# WIRELESS_UART.net
KiCad netlist of a schematic drawn in Altium Designer
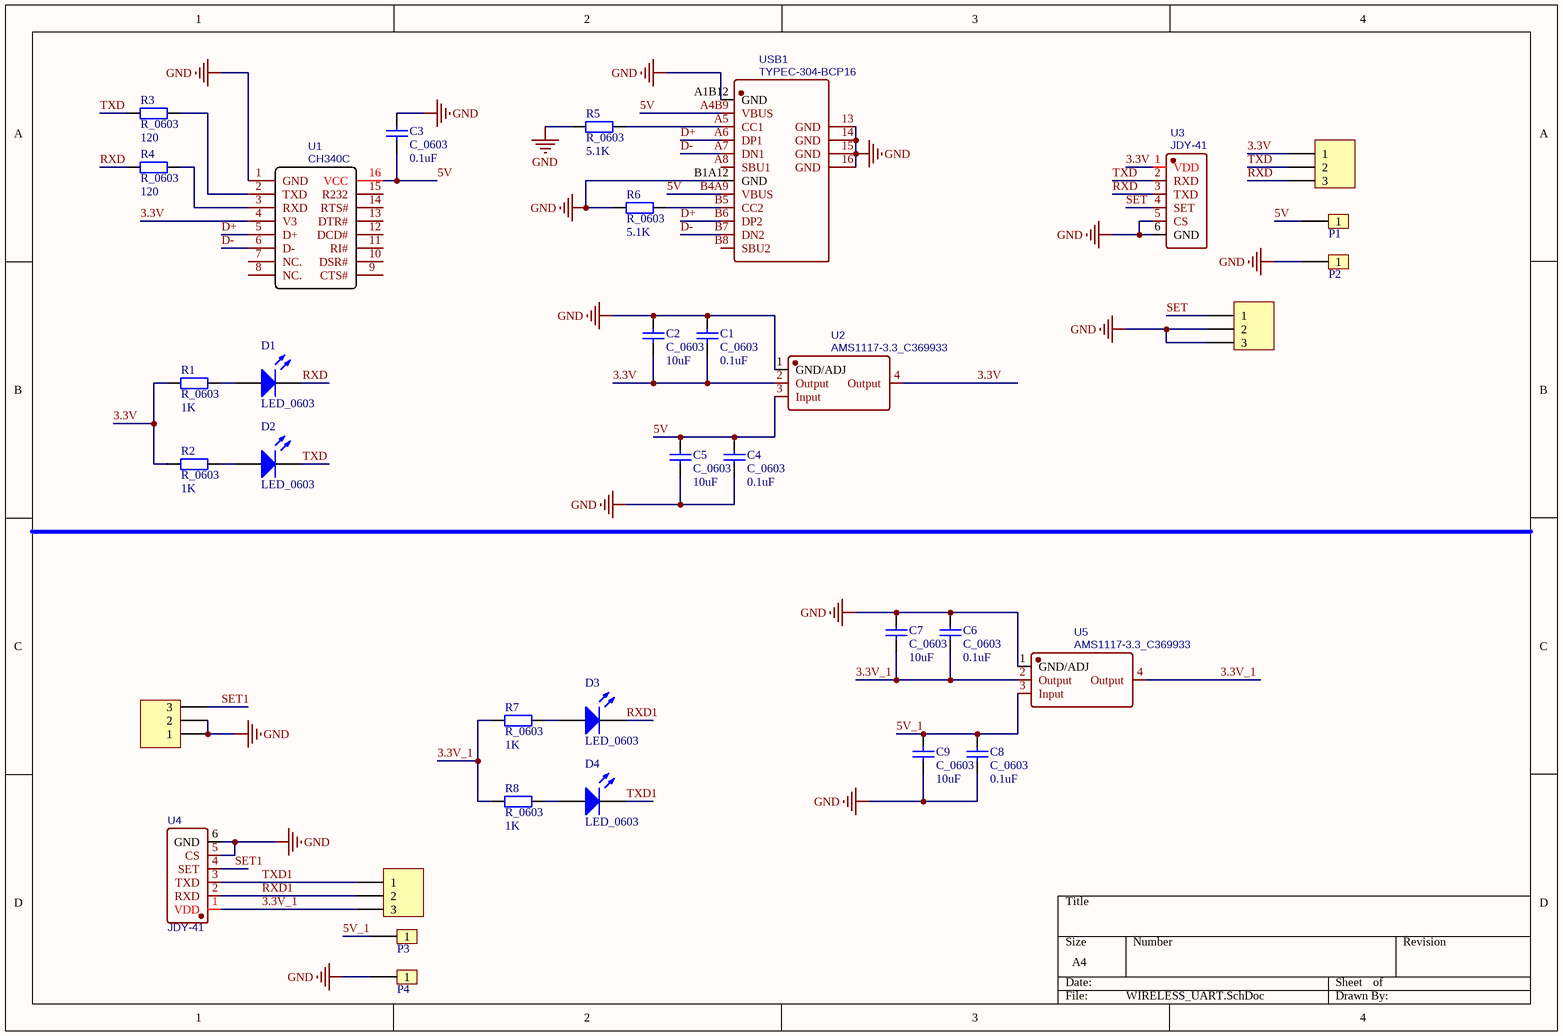
[diagram p0: WIRELESS_UART.SchDoc]

(export (version "E")
  (design (tool "Eeschema 10.0.6"))
  (components
    (comp (ref "C1")
      (value "C_0603")
      (footprint "C_0603")
      (fields (field (name "ALTIUM_VALUE") "0.1uF") (field (name "PUBLISHER") "Altium Limited"))
      (libsource (lib "WIRELESS_UART") (part "C_0603"))
    )
    (comp (ref "C2")
      (value "C_0603")
      (footprint "C1206 - duplicate")
      (fields (field (name "ALTIUM_VALUE") "10uF") (field (name "PUBLISHER") "Altium Limited"))
      (libsource (lib "WIRELESS_UART") (part "C_0603"))
    )
    (comp (ref "C3")
      (value "C_0603")
      (footprint "C_0603")
      (fields (field (name "ALTIUM_VALUE") "0.1uF") (field (name "PUBLISHER") "Altium Limited"))
      (libsource (lib "WIRELESS_UART") (part "C_0603"))
    )
    (comp (ref "C4")
      (value "C_0603")
      (footprint "C_0603")
      (fields (field (name "ALTIUM_VALUE") "0.1uF") (field (name "PUBLISHER") "Altium Limited"))
      (libsource (lib "WIRELESS_UART") (part "C_0603"))
    )
    (comp (ref "C5")
      (value "C_0603")
      (footprint "C1206 - duplicate")
      (fields (field (name "ALTIUM_VALUE") "10uF") (field (name "PUBLISHER") "Altium Limited"))
      (libsource (lib "WIRELESS_UART") (part "C_0603"))
    )
    (comp (ref "C6")
      (value "C_0603")
      (footprint "C_0603")
      (fields (field (name "ALTIUM_VALUE") "0.1uF") (field (name "PUBLISHER") "Altium Limited"))
      (libsource (lib "WIRELESS_UART") (part "C_0603"))
    )
    (comp (ref "C7")
      (value "C_0603")
      (footprint "C1206 - duplicate")
      (fields (field (name "ALTIUM_VALUE") "10uF") (field (name "PUBLISHER") "Altium Limited"))
      (libsource (lib "WIRELESS_UART") (part "C_0603"))
    )
    (comp (ref "C8")
      (value "C_0603")
      (footprint "C_0603")
      (fields (field (name "ALTIUM_VALUE") "0.1uF") (field (name "PUBLISHER") "Altium Limited"))
      (libsource (lib "WIRELESS_UART") (part "C_0603"))
    )
    (comp (ref "C9")
      (value "C_0603")
      (footprint "C1206 - duplicate")
      (fields (field (name "ALTIUM_VALUE") "10uF") (field (name "PUBLISHER") "Altium Limited"))
      (libsource (lib "WIRELESS_UART") (part "C_0603"))
    )
    (comp (ref "D1")
      (value "LED_0603")
      (footprint "LED-0603")
      (description "发光二极管")
      (fields (field (name "PUBLISHER") "Altium Limited"))
      (libsource (lib "WIRELESS_UART") (part "LED 0603"))
    )
    (comp (ref "D2")
      (value "LED_0603")
      (footprint "LED-0603")
      (description "发光二极管")
      (fields (field (name "PUBLISHER") "Altium Limited"))
      (libsource (lib "WIRELESS_UART") (part "LED 0603"))
    )
    (comp (ref "D3")
      (value "LED_0603")
      (footprint "LED-0603")
      (description "发光二极管")
      (fields (field (name "PUBLISHER") "Altium Limited"))
      (libsource (lib "WIRELESS_UART") (part "LED 0603"))
    )
    (comp (ref "D4")
      (value "LED_0603")
      (footprint "LED-0603")
      (description "发光二极管")
      (fields (field (name "PUBLISHER") "Altium Limited"))
      (libsource (lib "WIRELESS_UART") (part "LED 0603"))
    )
    (comp (ref "P1")
      (value "Header 1")
      (footprint "HEADER1")
      (fields (field (name "PUBLISHER") "Altium Limited"))
      (libsource (lib "WIRELESS_UART") (part "Header 1"))
    )
    (comp (ref "P2")
      (value "Header 1")
      (footprint "HEADER1")
      (fields (field (name "PUBLISHER") "Altium Limited"))
      (libsource (lib "WIRELESS_UART") (part "Header 1"))
    )
    (comp (ref "P3")
      (value "Header 1")
      (footprint "HEADER1")
      (fields (field (name "PUBLISHER") "Altium Limited"))
      (libsource (lib "WIRELESS_UART") (part "Header 1"))
    )
    (comp (ref "P4")
      (value "Header 1")
      (footprint "HEADER1")
      (fields (field (name "PUBLISHER") "Altium Limited"))
      (libsource (lib "WIRELESS_UART") (part "Header 1"))
    )
    (comp (ref "R1")
      (value "R_0603")
      (footprint "R_0603")
      (fields (field (name "ALTIUM_VALUE") "1K") (field (name "PUBLISHER") "Altium Limited"))
      (libsource (lib "WIRELESS_UART") (part "R_0603"))
    )
    (comp (ref "R2")
      (value "R_0603")
      (footprint "R_0603")
      (fields (field (name "ALTIUM_VALUE") "1K") (field (name "PUBLISHER") "Altium Limited"))
      (libsource (lib "WIRELESS_UART") (part "R_0603"))
    )
    (comp (ref "R3")
      (value "R_0603")
      (footprint "R_0603")
      (fields (field (name "ALTIUM_VALUE") "120") (field (name "PUBLISHER") "Altium Limited"))
      (libsource (lib "WIRELESS_UART") (part "R_0603"))
    )
    (comp (ref "R4")
      (value "R_0603")
      (footprint "R_0603")
      (fields (field (name "ALTIUM_VALUE") "120") (field (name "PUBLISHER") "Altium Limited"))
      (libsource (lib "WIRELESS_UART") (part "R_0603"))
    )
    (comp (ref "R5")
      (value "R_0603")
      (footprint "R_0603")
      (fields (field (name "ALTIUM_VALUE") "5.1K") (field (name "PUBLISHER") "Altium Limited"))
      (libsource (lib "WIRELESS_UART") (part "R_0603"))
    )
    (comp (ref "R6")
      (value "R_0603")
      (footprint "R_0603")
      (fields (field (name "ALTIUM_VALUE") "5.1K") (field (name "PUBLISHER") "Altium Limited"))
      (libsource (lib "") (part "R_0603_1"))
    )
    (comp (ref "R7")
      (value "R_0603")
      (footprint "R_0603")
      (fields (field (name "ALTIUM_VALUE") "1K") (field (name "PUBLISHER") "Altium Limited"))
      (libsource (lib "WIRELESS_UART") (part "R_0603"))
    )
    (comp (ref "R8")
      (value "R_0603")
      (footprint "R_0603")
      (fields (field (name "ALTIUM_VALUE") "1K") (field (name "PUBLISHER") "Altium Limited"))
      (libsource (lib "WIRELESS_UART") (part "R_0603"))
    )
    (comp (ref "SWD1")
      (value "SWD")
      (footprint "SH1_0X5P_WT")
      (description "SWD下载")
      (fields (field (name "PUBLISHER") "Altium Limited"))
      (libsource (lib "") (part "SWD_1"))
    )
    (comp (ref "SWD2")
      (value "SWD")
      (footprint "SH1_0X5P_WT")
      (description "SWD下载")
      (fields (field (name "PUBLISHER") "Altium Limited"))
      (libsource (lib "") (part "SWD_1"))
    )
    (comp (ref "SWD3")
      (value "SWD4")
      (footprint "SH1_0X5P_WT")
      (description "SWD下载")
      (fields (field (name "PUBLISHER") "Altium Limited"))
      (libsource (lib "WIRELESS_UART") (part "SWD"))
    )
    (comp (ref "SWD4")
      (value "SWD")
      (footprint "SH1_0X5P_WT")
      (description "SWD下载")
      (fields (field (name "PUBLISHER") "Altium Limited"))
      (libsource (lib "") (part "SWD_1"))
    )
    (comp (ref "U1")
      (value "CH340C")
      (footprint "CH340C")
      (fields (field (name "BOM_SUPPLIER PART") "C84681"))
      (libsource (lib "altium-import") (part "root_0_CH340C_"))
    )
    (comp (ref "U2")
      (value "AMS1117-3.3_C369933")
      (footprint "AMS1117")
      (fields
        (field (name "BOM_SUPPLIER PART") "C369933")
        (field (name "BOM_MANUFACTURER PART") "AMS1117-3.3")
        (field (name "CONTRIBUTOR") "LCSC")
      )
      (libsource (lib "altium-import") (part "root_0_AMS1117-3.3_C369933_"))
    )
    (comp (ref "U3")
      (value "JDY-41")
      (footprint "2.4GMODLE")
      (fields
        (field (name "BOM_SUPPLIER PART") "C2837202")
        (field (name "BOM_MANUFACTURER PART") "M-BK2461U")
        (field (name "CONTRIBUTOR") "LCSC")
      )
      (libsource (lib "altium-import") (part "root_0_M-BK2461U_"))
    )
    (comp (ref "U4")
      (value "JDY-41")
      (footprint "2.4GMODLE")
      (fields
        (field (name "BOM_SUPPLIER PART") "C2837202")
        (field (name "BOM_MANUFACTURER PART") "M-BK2461U")
        (field (name "CONTRIBUTOR") "LCSC")
      )
      (libsource (lib "altium-import") (part "root_2_M-BK2461U_"))
    )
    (comp (ref "U5")
      (value "AMS1117-3.3_C369933")
      (footprint "AMS1117")
      (fields
        (field (name "BOM_SUPPLIER PART") "C369933")
        (field (name "BOM_MANUFACTURER PART") "AMS1117-3.3")
        (field (name "CONTRIBUTOR") "LCSC")
      )
      (libsource (lib "altium-import") (part "root_0_AMS1117-3.3_C369933_"))
    )
    (comp (ref "USB1")
      (value "TYPEC-304-BCP16")
      (footprint "TYPE_C")
      (fields (field (name "BOM_SUPPLIER PART") "C720629") (field (name "CONTRIBUTOR") "LCSC"))
      (libsource (lib "altium-import") (part "root_0_TYPEC-304-BCP16_"))
    )
  )
  (nets
    (net (code "1") (name "/3.3V") (class "Default")
      (node (ref "C1") (pin "1") (pinfunction "1_1") (pintype "passive"))
      (node (ref "C2") (pin "1") (pinfunction "1_1") (pintype "passive"))
      (node (ref "R1") (pin "1") (pinfunction "1_1") (pintype "passive"))
      (node (ref "R2") (pin "1") (pinfunction "1_1") (pintype "passive"))
      (node (ref "SWD1") (pin "1") (pinfunction "1_1") (pintype "passive"))
      (node (ref "U1") (pin "4") (pinfunction "V3_4") (pintype "passive"))
      (node (ref "U2") (pin "2") (pinfunction "Output_2") (pintype "passive"))
      (node (ref "U2") (pin "4") (pinfunction "Output_4") (pintype "passive"))
      (node (ref "U3") (pin "1") (pinfunction "VDD_1") (pintype "passive"))
    )
    (net (code "2") (name "/3.3V_1") (class "Default")
      (node (ref "C6") (pin "1") (pinfunction "1_1") (pintype "passive"))
      (node (ref "C7") (pin "1") (pinfunction "1_1") (pintype "passive"))
      (node (ref "R7") (pin "1") (pinfunction "1_1") (pintype "passive"))
      (node (ref "R8") (pin "1") (pinfunction "1_1") (pintype "passive"))
      (node (ref "SWD4") (pin "3") (pinfunction "3_3") (pintype "passive"))
      (node (ref "U4") (pin "1") (pinfunction "VDD_1") (pintype "passive"))
      (node (ref "U5") (pin "2") (pinfunction "Output_2") (pintype "passive"))
      (node (ref "U5") (pin "4") (pinfunction "Output_4") (pintype "passive"))
    )
    (net (code "3") (name "/5V") (class "Default")
      (node (ref "C3") (pin "1") (pinfunction "1_1") (pintype "passive"))
      (node (ref "C4") (pin "2") (pinfunction "2_2") (pintype "passive"))
      (node (ref "C5") (pin "2") (pinfunction "2_2") (pintype "passive"))
      (node (ref "P1") (pin "1") (pinfunction "1_1") (pintype "passive"))
      (node (ref "U1") (pin "16") (pinfunction "VCC_16") (pintype "passive"))
      (node (ref "U2") (pin "3") (pinfunction "Input_3") (pintype "passive"))
      (node (ref "USB1") (pin "A4B9") (pinfunction "VBUS_A4B9") (pintype "passive"))
      (node (ref "USB1") (pin "B4A9") (pinfunction "VBUS_B4A9") (pintype "passive"))
    )
    (net (code "4") (name "/5V_1") (class "Default")
      (node (ref "C8") (pin "2") (pinfunction "2_2") (pintype "passive"))
      (node (ref "C9") (pin "2") (pinfunction "2_2") (pintype "passive"))
      (node (ref "P3") (pin "1") (pinfunction "1_1") (pintype "passive"))
      (node (ref "U5") (pin "3") (pinfunction "Input_3") (pintype "passive"))
    )
    (net (code "5") (name "/D+") (class "Default")
      (node (ref "U1") (pin "5") (pinfunction "D+_5") (pintype "passive"))
      (node (ref "USB1") (pin "A6") (pinfunction "DP1_A6") (pintype "passive"))
      (node (ref "USB1") (pin "B6") (pinfunction "DP2_B6") (pintype "passive"))
    )
    (net (code "6") (name "/D-") (class "Default")
      (node (ref "U1") (pin "6") (pinfunction "D-_6") (pintype "passive"))
      (node (ref "USB1") (pin "A7") (pinfunction "DN1_A7") (pintype "passive"))
      (node (ref "USB1") (pin "B7") (pinfunction "DN2_B7") (pintype "passive"))
    )
    (net (code "7") (name "/RXD") (class "Default")
      (node (ref "D1") (pin "2") (pinfunction "2_2") (pintype "passive"))
      (node (ref "R4") (pin "1") (pinfunction "1_1") (pintype "passive"))
      (node (ref "SWD1") (pin "3") (pinfunction "3_3") (pintype "passive"))
      (node (ref "U3") (pin "3") (pinfunction "TXD_3") (pintype "passive"))
    )
    (net (code "8") (name "/RXD1") (class "Default")
      (node (ref "D3") (pin "2") (pinfunction "2_2") (pintype "passive"))
      (node (ref "SWD4") (pin "2") (pinfunction "2_2") (pintype "passive"))
      (node (ref "U4") (pin "2") (pinfunction "RXD_2") (pintype "passive"))
    )
    (net (code "9") (name "/SET") (class "Default")
      (node (ref "SWD2") (pin "1") (pinfunction "1_1") (pintype "passive"))
      (node (ref "U3") (pin "4") (pinfunction "SET_4") (pintype "passive"))
    )
    (net (code "10") (name "/SET1") (class "Default")
      (node (ref "SWD3") (pin "3") (pinfunction "3_3") (pintype "passive"))
      (node (ref "U4") (pin "4") (pinfunction "SET_4") (pintype "passive"))
    )
    (net (code "11") (name "/TXD") (class "Default")
      (node (ref "D2") (pin "2") (pinfunction "2_2") (pintype "passive"))
      (node (ref "R3") (pin "1") (pinfunction "1_1") (pintype "passive"))
      (node (ref "SWD1") (pin "2") (pinfunction "2_2") (pintype "passive"))
      (node (ref "U3") (pin "2") (pinfunction "RXD_2") (pintype "passive"))
    )
    (net (code "12") (name "/TXD1") (class "Default")
      (node (ref "D4") (pin "2") (pinfunction "2_2") (pintype "passive"))
      (node (ref "SWD4") (pin "1") (pinfunction "1_1") (pintype "passive"))
      (node (ref "U4") (pin "3") (pinfunction "TXD_3") (pintype "passive"))
    )
    (net (code "13") (name "GND") (class "Default")
      (node (ref "C1") (pin "2") (pinfunction "2_2") (pintype "passive"))
      (node (ref "C2") (pin "2") (pinfunction "2_2") (pintype "passive"))
      (node (ref "C3") (pin "2") (pinfunction "2_2") (pintype "passive"))
      (node (ref "C4") (pin "1") (pinfunction "1_1") (pintype "passive"))
      (node (ref "C5") (pin "1") (pinfunction "1_1") (pintype "passive"))
      (node (ref "C6") (pin "2") (pinfunction "2_2") (pintype "passive"))
      (node (ref "C7") (pin "2") (pinfunction "2_2") (pintype "passive"))
      (node (ref "C8") (pin "1") (pinfunction "1_1") (pintype "passive"))
      (node (ref "C9") (pin "1") (pinfunction "1_1") (pintype "passive"))
      (node (ref "P2") (pin "1") (pinfunction "1_1") (pintype "passive"))
      (node (ref "P4") (pin "1") (pinfunction "1_1") (pintype "passive"))
      (node (ref "R5") (pin "1") (pinfunction "1_1") (pintype "passive"))
      (node (ref "R6") (pin "2") (pinfunction "2_2") (pintype "passive"))
      (node (ref "SWD2") (pin "2") (pinfunction "2_2") (pintype "passive"))
      (node (ref "SWD2") (pin "3") (pinfunction "3_3") (pintype "passive"))
      (node (ref "SWD3") (pin "1") (pinfunction "1_1") (pintype "passive"))
      (node (ref "SWD3") (pin "2") (pinfunction "2_2") (pintype "passive"))
      (node (ref "U1") (pin "1") (pinfunction "GND_1") (pintype "passive"))
      (node (ref "U2") (pin "1") (pinfunction "GND/ADJ_1") (pintype "passive"))
      (node (ref "U3") (pin "5") (pinfunction "CS_5") (pintype "passive"))
      (node (ref "U3") (pin "6") (pinfunction "GND_6") (pintype "passive"))
      (node (ref "U4") (pin "5") (pinfunction "CS_5") (pintype "passive"))
      (node (ref "U4") (pin "6") (pinfunction "GND_6") (pintype "passive"))
      (node (ref "U5") (pin "1") (pinfunction "GND/ADJ_1") (pintype "passive"))
      (node (ref "USB1") (pin "13") (pinfunction "GND_13") (pintype "passive"))
      (node (ref "USB1") (pin "14") (pinfunction "GND_14") (pintype "passive"))
      (node (ref "USB1") (pin "15") (pinfunction "GND_15") (pintype "passive"))
      (node (ref "USB1") (pin "16") (pinfunction "GND_16") (pintype "passive"))
      (node (ref "USB1") (pin "A1B12") (pinfunction "GND_A1B12") (pintype "passive"))
      (node (ref "USB1") (pin "B1A12") (pinfunction "GND_B1A12") (pintype "passive"))
    )
    (net (code "14") (name "Net-(D1-Pad1)") (class "Default")
      (node (ref "D1") (pin "1") (pinfunction "1_1") (pintype "passive"))
      (node (ref "R1") (pin "2") (pinfunction "2_2") (pintype "passive"))
    )
    (net (code "15") (name "Net-(D2-Pad1)") (class "Default")
      (node (ref "D2") (pin "1") (pinfunction "1_1") (pintype "passive"))
      (node (ref "R2") (pin "2") (pinfunction "2_2") (pintype "passive"))
    )
    (net (code "16") (name "Net-(D3-Pad1)") (class "Default")
      (node (ref "D3") (pin "1") (pinfunction "1_1") (pintype "passive"))
      (node (ref "R7") (pin "2") (pinfunction "2_2") (pintype "passive"))
    )
    (net (code "17") (name "Net-(D4-Pad1)") (class "Default")
      (node (ref "D4") (pin "1") (pinfunction "1_1") (pintype "passive"))
      (node (ref "R8") (pin "2") (pinfunction "2_2") (pintype "passive"))
    )
    (net (code "18") (name "Net-(U1-RXD)") (class "Default")
      (node (ref "R4") (pin "2") (pinfunction "2_2") (pintype "passive"))
      (node (ref "U1") (pin "3") (pinfunction "RXD_3") (pintype "passive"))
    )
    (net (code "19") (name "Net-(U1-TXD)") (class "Default")
      (node (ref "R3") (pin "2") (pinfunction "2_2") (pintype "passive"))
      (node (ref "U1") (pin "2") (pinfunction "TXD_2") (pintype "passive"))
    )
    (net (code "20") (name "Net-(USB1-CC1)") (class "Default")
      (node (ref "R5") (pin "2") (pinfunction "2_2") (pintype "passive"))
      (node (ref "USB1") (pin "A5") (pinfunction "CC1_A5") (pintype "passive"))
    )
    (net (code "21") (name "Net-(USB1-CC2)") (class "Default")
      (node (ref "R6") (pin "1") (pinfunction "1_1") (pintype "passive"))
      (node (ref "USB1") (pin "B5") (pinfunction "CC2_B5") (pintype "passive"))
    )
    (net (code "22") (name "unconnected-(U1-CTS#-Pad9)") (class "Default")
      (node (ref "U1") (pin "9") (pinfunction "CTS#_9") (pintype "passive"))
    )
    (net (code "23") (name "unconnected-(U1-DCD#-Pad12)") (class "Default")
      (node (ref "U1") (pin "12") (pinfunction "DCD#_12") (pintype "passive"))
    )
    (net (code "24") (name "unconnected-(U1-DSR#-Pad10)") (class "Default")
      (node (ref "U1") (pin "10") (pinfunction "DSR#_10") (pintype "passive"))
    )
    (net (code "25") (name "unconnected-(U1-DTR#-Pad13)") (class "Default")
      (node (ref "U1") (pin "13") (pinfunction "DTR#_13") (pintype "passive"))
    )
    (net (code "26") (name "unconnected-(U1-NC.-Pad7)") (class "Default")
      (node (ref "U1") (pin "7") (pinfunction "NC._7") (pintype "passive"))
    )
    (net (code "27") (name "unconnected-(U1-NC.-Pad8)") (class "Default")
      (node (ref "U1") (pin "8") (pinfunction "NC._8") (pintype "passive"))
    )
    (net (code "28") (name "unconnected-(U1-R232-Pad15)") (class "Default")
      (node (ref "U1") (pin "15") (pinfunction "R232_15") (pintype "passive"))
    )
    (net (code "29") (name "unconnected-(U1-RI#-Pad11)") (class "Default")
      (node (ref "U1") (pin "11") (pinfunction "RI#_11") (pintype "passive"))
    )
    (net (code "30") (name "unconnected-(U1-RTS#-Pad14)") (class "Default")
      (node (ref "U1") (pin "14") (pinfunction "RTS#_14") (pintype "passive"))
    )
    (net (code "31") (name "unconnected-(USB1-SBU1-PadA8)") (class "Default")
      (node (ref "USB1") (pin "A8") (pinfunction "SBU1_A8") (pintype "passive"))
    )
    (net (code "32") (name "unconnected-(USB1-SBU2-PadB8)") (class "Default")
      (node (ref "USB1") (pin "B8") (pinfunction "SBU2_B8") (pintype "passive"))
    )
  )
)
